# Sheet1.net
KiCad netlist of a schematic drawn in Altium Designer
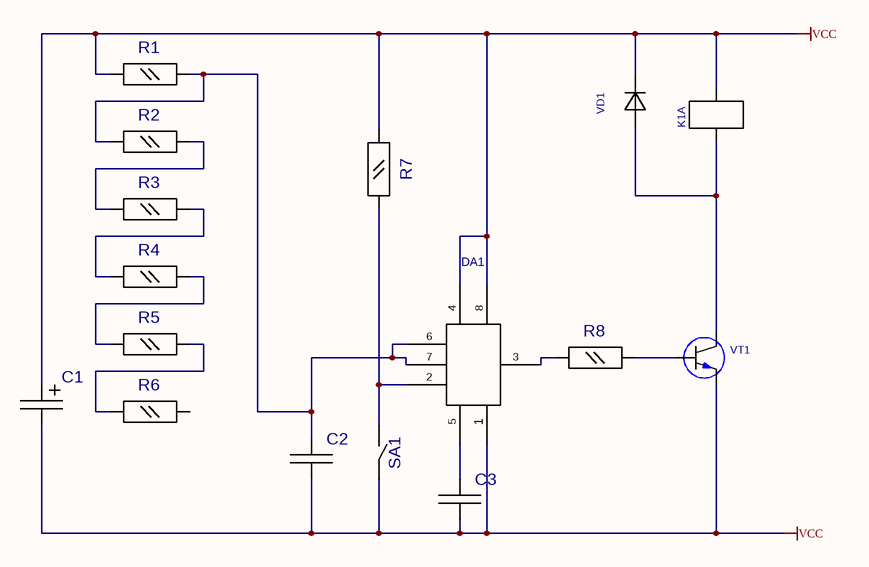
[diagram p0: Sheet1.SCHDOC]

(export (version "E")
  (design (tool "Eeschema 10.0.6"))
  (components
    (comp (ref "C1") (value "CE3528-B") (footprint "CE3528-B") (libsource (lib "*") (part "CE3528-B")))
    (comp (ref "C2") (value "CC1812") (footprint "CC1812") (libsource (lib "*") (part "CC1812")))
    (comp (ref "C3") (value "CC1812") (footprint "CC1812") (libsource (lib "*") (part "CC1812")))
    (comp (ref "DA1") (value "LMC555") (footprint "LMC555") (libsource (lib "*") (part "LMC555")))
    (comp (ref "K1") (value "РЭС 49") (footprint "RES49") (libsource (lib "*") (part "РЭС 49")))
    (comp (ref "R1")
      (value "C2-33H-0.125W_OLD_UGO")
      (footprint "C2-33H-0.125W")
      (fields (field (name "AUTOR") "pcbdesigner.ru"))
      (libsource (lib "*") (part "C2-33H-0.125W_OLD_UGO"))
    )
    (comp (ref "R2")
      (value "C2-33H-0.125W_OLD_UGO")
      (footprint "C2-33H-0.125W")
      (fields (field (name "AUTOR") "pcbdesigner.ru"))
      (libsource (lib "*") (part "C2-33H-0.125W_OLD_UGO"))
    )
    (comp (ref "R3")
      (value "C2-33H-0.125W_OLD_UGO")
      (footprint "C2-33H-0.125W")
      (fields (field (name "AUTOR") "pcbdesigner.ru"))
      (libsource (lib "*") (part "C2-33H-0.125W_OLD_UGO"))
    )
    (comp (ref "R4")
      (value "C2-33H-0.125W_OLD_UGO")
      (footprint "C2-33H-0.125W")
      (fields (field (name "AUTOR") "pcbdesigner.ru"))
      (libsource (lib "*") (part "C2-33H-0.125W_OLD_UGO"))
    )
    (comp (ref "R5")
      (value "C2-33H-0.125W_OLD_UGO")
      (footprint "C2-33H-0.125W")
      (fields (field (name "AUTOR") "pcbdesigner.ru"))
      (libsource (lib "*") (part "C2-33H-0.125W_OLD_UGO"))
    )
    (comp (ref "R6")
      (value "C2-33H-0.125W_OLD_UGO")
      (footprint "C2-33H-0.125W")
      (fields (field (name "AUTOR") "pcbdesigner.ru"))
      (libsource (lib "*") (part "C2-33H-0.125W_OLD_UGO"))
    )
    (comp (ref "R7")
      (value "C2-33H-0.125W_OLD_UGO")
      (footprint "C2-33H-0.125W")
      (fields (field (name "AUTOR") "pcbdesigner.ru"))
      (libsource (lib "*") (part "C2-33H-0.125W_OLD_UGO"))
    )
    (comp (ref "R8")
      (value "C2-33H-0.125W_OLD_UGO")
      (footprint "C2-33H-0.125W")
      (fields (field (name "AUTOR") "pcbdesigner.ru"))
      (libsource (lib "*") (part "C2-33H-0.125W_OLD_UGO"))
    )
    (comp (ref "SA1")
      (value "8AS9M2RE")
      (footprint "8AS9M2RE")
      (fields (field (name "AUTHOR") "pcbdesigner.ru"))
      (libsource (lib "*") (part "8AS9M2RE"))
    )
    (comp (ref "VD1") (value "D-6") (footprint "D6") (libsource (lib "*") (part "D-6")))
    (comp (ref "VT1") (value "KT201") (footprint "TO-18") (libsource (lib "*") (part "KT201")))
  )
  (nets
    (net (code "1") (name "Net-(C2-Pad1)") (class "Default")
      (node (ref "C2") (pin "1") (pinfunction "1_1") (pintype "passive"))
      (node (ref "DA1") (pin "6") (pintype "passive"))
      (node (ref "DA1") (pin "7") (pintype "passive"))
      (node (ref "R1") (pin "1") (pinfunction "1_1") (pintype "passive"))
      (node (ref "R2") (pin "2") (pinfunction "2_2") (pintype "passive"))
    )
    (net (code "2") (name "Net-(C3-Pad1)") (class "Default")
      (node (ref "C3") (pin "1") (pinfunction "1_1") (pintype "passive"))
      (node (ref "DA1") (pin "5") (pintype "passive"))
    )
    (net (code "3") (name "Net-(DA1-Pad2)") (class "Default")
      (node (ref "DA1") (pin "2") (pintype "passive"))
      (node (ref "R7") (pin "1") (pinfunction "1_1") (pintype "passive"))
      (node (ref "SA1") (pin "1") (pinfunction "1_1") (pintype "passive"))
    )
    (net (code "4") (name "Net-(DA1-Pad3)") (class "Default")
      (node (ref "DA1") (pin "3") (pintype "passive"))
      (node (ref "R8") (pin "2") (pinfunction "2_2") (pintype "passive"))
    )
    (net (code "5") (name "Net-(K1-Pad4)") (class "Default")
      (node (ref "K1") (pin "4") (pintype "passive"))
      (node (ref "VD1") (pin "1") (pintype "passive"))
      (node (ref "VT1") (pin "1") (pintype "passive"))
    )
    (net (code "6") (name "Net-(R2-Pad1)") (class "Default")
      (node (ref "R2") (pin "1") (pinfunction "1_1") (pintype "passive"))
      (node (ref "R3") (pin "2") (pinfunction "2_2") (pintype "passive"))
    )
    (net (code "7") (name "Net-(R3-Pad1)") (class "Default")
      (node (ref "R3") (pin "1") (pinfunction "1_1") (pintype "passive"))
      (node (ref "R4") (pin "2") (pinfunction "2_2") (pintype "passive"))
    )
    (net (code "8") (name "Net-(R4-Pad1)") (class "Default")
      (node (ref "R4") (pin "1") (pinfunction "1_1") (pintype "passive"))
      (node (ref "R5") (pin "2") (pinfunction "2_2") (pintype "passive"))
    )
    (net (code "9") (name "Net-(R5-Pad1)") (class "Default")
      (node (ref "R5") (pin "1") (pinfunction "1_1") (pintype "passive"))
      (node (ref "R6") (pin "2") (pinfunction "2_2") (pintype "passive"))
    )
    (net (code "10") (name "Net-(R8-Pad1)") (class "Default")
      (node (ref "R8") (pin "1") (pinfunction "1_1") (pintype "passive"))
      (node (ref "VT1") (pin "3") (pintype "passive"))
    )
    (net (code "11") (name "VCC") (class "Default")
      (node (ref "C1") (pin "1") (pinfunction "i/o_1") (pintype "passive"))
      (node (ref "C1") (pin "2") (pinfunction "i/o1_2") (pintype "passive"))
      (node (ref "C2") (pin "2") (pinfunction "2_2") (pintype "passive"))
      (node (ref "C3") (pin "2") (pinfunction "2_2") (pintype "passive"))
      (node (ref "DA1") (pin "1") (pintype "passive"))
      (node (ref "DA1") (pin "4") (pintype "passive"))
      (node (ref "DA1") (pin "8") (pintype "passive"))
      (node (ref "K1") (pin "5") (pintype "passive"))
      (node (ref "R1") (pin "2") (pinfunction "2_2") (pintype "passive"))
      (node (ref "R7") (pin "2") (pinfunction "2_2") (pintype "passive"))
      (node (ref "SA1") (pin "2") (pinfunction "2_2") (pintype "passive"))
      (node (ref "VD1") (pin "2") (pintype "passive"))
      (node (ref "VT1") (pin "2") (pintype "passive"))
    )
    (net (code "12") (name "unconnected-(R6-Pad1)") (class "Default")
      (node (ref "R6") (pin "1") (pinfunction "1_1") (pintype "passive"))
    )
  )
)
